# FE_LED.net
KiCad netlist of a schematic drawn in EAGLE
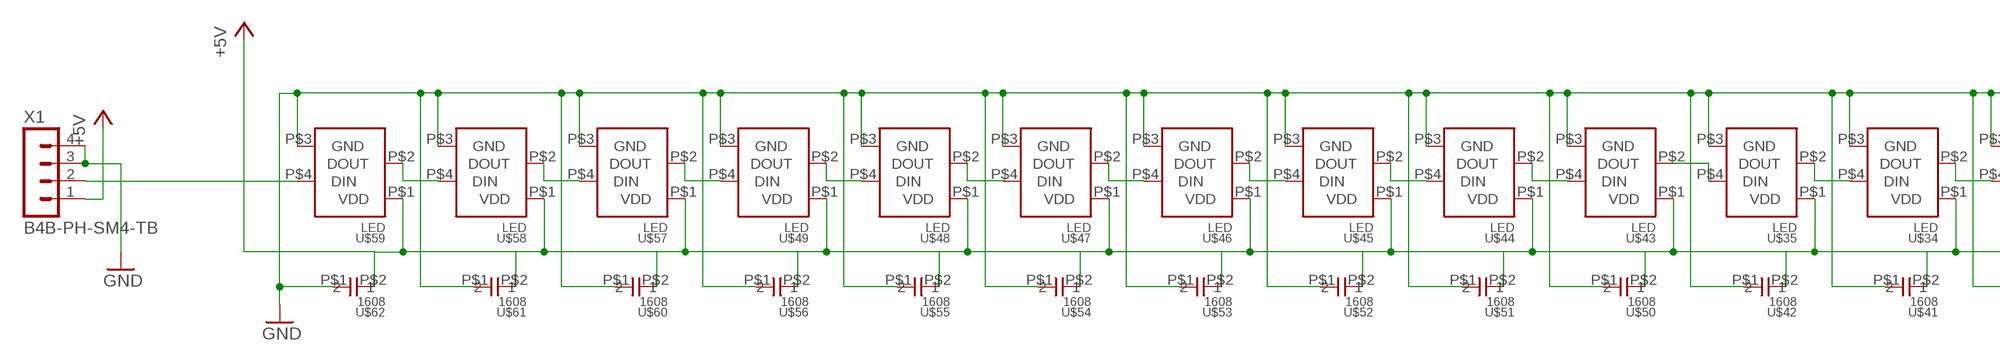
[diagram p0: schematic, sheet 1, part 1 of 2]
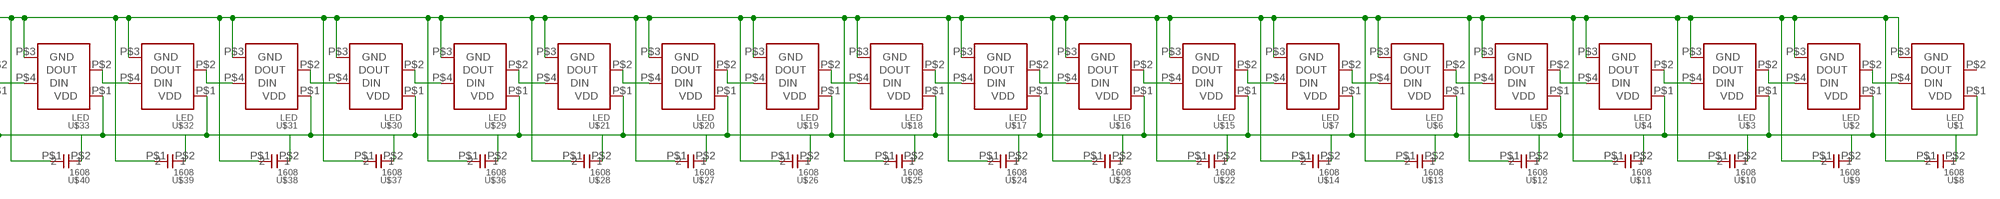
[diagram p1: schematic, sheet 1, part 2 of 2]

(export (version "E")
  (design (tool "Eeschema 10.0.6"))
  (components
    (comp (ref "U$1")
      (value "LED")
      (footprint "eagle-import:LED")
      (libsource (lib "eagle-import") (part "LED"))
    )
    (comp (ref "U$2")
      (value "LED")
      (footprint "eagle-import:LED")
      (libsource (lib "eagle-import") (part "LED"))
    )
    (comp (ref "U$3")
      (value "LED")
      (footprint "eagle-import:LED")
      (libsource (lib "eagle-import") (part "LED"))
    )
    (comp (ref "U$4")
      (value "LED")
      (footprint "eagle-import:LED")
      (libsource (lib "eagle-import") (part "LED"))
    )
    (comp (ref "U$5")
      (value "LED")
      (footprint "eagle-import:LED")
      (libsource (lib "eagle-import") (part "LED"))
    )
    (comp (ref "U$6")
      (value "LED")
      (footprint "eagle-import:LED")
      (libsource (lib "eagle-import") (part "LED"))
    )
    (comp (ref "U$7")
      (value "LED")
      (footprint "eagle-import:LED")
      (libsource (lib "eagle-import") (part "LED"))
    )
    (comp (ref "U$8")
      (value "1608")
      (footprint "eagle-import:CON")
      (libsource (lib "eagle-import") (part "1608"))
    )
    (comp (ref "U$9")
      (value "1608")
      (footprint "eagle-import:CON")
      (libsource (lib "eagle-import") (part "1608"))
    )
    (comp (ref "U$10")
      (value "1608")
      (footprint "eagle-import:CON")
      (libsource (lib "eagle-import") (part "1608"))
    )
    (comp (ref "U$11")
      (value "1608")
      (footprint "eagle-import:CON")
      (libsource (lib "eagle-import") (part "1608"))
    )
    (comp (ref "U$12")
      (value "1608")
      (footprint "eagle-import:CON")
      (libsource (lib "eagle-import") (part "1608"))
    )
    (comp (ref "U$13")
      (value "1608")
      (footprint "eagle-import:CON")
      (libsource (lib "eagle-import") (part "1608"))
    )
    (comp (ref "U$14")
      (value "1608")
      (footprint "eagle-import:CON")
      (libsource (lib "eagle-import") (part "1608"))
    )
    (comp (ref "U$15")
      (value "LED")
      (footprint "eagle-import:LED")
      (libsource (lib "eagle-import") (part "LED"))
    )
    (comp (ref "U$16")
      (value "LED")
      (footprint "eagle-import:LED")
      (libsource (lib "eagle-import") (part "LED"))
    )
    (comp (ref "U$17")
      (value "LED")
      (footprint "eagle-import:LED")
      (libsource (lib "eagle-import") (part "LED"))
    )
    (comp (ref "U$18")
      (value "LED")
      (footprint "eagle-import:LED")
      (libsource (lib "eagle-import") (part "LED"))
    )
    (comp (ref "U$19")
      (value "LED")
      (footprint "eagle-import:LED")
      (libsource (lib "eagle-import") (part "LED"))
    )
    (comp (ref "U$20")
      (value "LED")
      (footprint "eagle-import:LED")
      (libsource (lib "eagle-import") (part "LED"))
    )
    (comp (ref "U$21")
      (value "LED")
      (footprint "eagle-import:LED")
      (libsource (lib "eagle-import") (part "LED"))
    )
    (comp (ref "U$22")
      (value "1608")
      (footprint "eagle-import:CON")
      (libsource (lib "eagle-import") (part "1608"))
    )
    (comp (ref "U$23")
      (value "1608")
      (footprint "eagle-import:CON")
      (libsource (lib "eagle-import") (part "1608"))
    )
    (comp (ref "U$24")
      (value "1608")
      (footprint "eagle-import:CON")
      (libsource (lib "eagle-import") (part "1608"))
    )
    (comp (ref "U$25")
      (value "1608")
      (footprint "eagle-import:CON")
      (libsource (lib "eagle-import") (part "1608"))
    )
    (comp (ref "U$26")
      (value "1608")
      (footprint "eagle-import:CON")
      (libsource (lib "eagle-import") (part "1608"))
    )
    (comp (ref "U$27")
      (value "1608")
      (footprint "eagle-import:CON")
      (libsource (lib "eagle-import") (part "1608"))
    )
    (comp (ref "U$28")
      (value "1608")
      (footprint "eagle-import:CON")
      (libsource (lib "eagle-import") (part "1608"))
    )
    (comp (ref "U$29")
      (value "LED")
      (footprint "eagle-import:LED")
      (libsource (lib "eagle-import") (part "LED"))
    )
    (comp (ref "U$30")
      (value "LED")
      (footprint "eagle-import:LED")
      (libsource (lib "eagle-import") (part "LED"))
    )
    (comp (ref "U$31")
      (value "LED")
      (footprint "eagle-import:LED")
      (libsource (lib "eagle-import") (part "LED"))
    )
    (comp (ref "U$32")
      (value "LED")
      (footprint "eagle-import:LED")
      (libsource (lib "eagle-import") (part "LED"))
    )
    (comp (ref "U$33")
      (value "LED")
      (footprint "eagle-import:LED")
      (libsource (lib "eagle-import") (part "LED"))
    )
    (comp (ref "U$34")
      (value "LED")
      (footprint "eagle-import:LED")
      (libsource (lib "eagle-import") (part "LED"))
    )
    (comp (ref "U$35")
      (value "LED")
      (footprint "eagle-import:LED")
      (libsource (lib "eagle-import") (part "LED"))
    )
    (comp (ref "U$36")
      (value "1608")
      (footprint "eagle-import:CON")
      (libsource (lib "eagle-import") (part "1608"))
    )
    (comp (ref "U$37")
      (value "1608")
      (footprint "eagle-import:CON")
      (libsource (lib "eagle-import") (part "1608"))
    )
    (comp (ref "U$38")
      (value "1608")
      (footprint "eagle-import:CON")
      (libsource (lib "eagle-import") (part "1608"))
    )
    (comp (ref "U$39")
      (value "1608")
      (footprint "eagle-import:CON")
      (libsource (lib "eagle-import") (part "1608"))
    )
    (comp (ref "U$40")
      (value "1608")
      (footprint "eagle-import:CON")
      (libsource (lib "eagle-import") (part "1608"))
    )
    (comp (ref "U$41")
      (value "1608")
      (footprint "eagle-import:CON")
      (libsource (lib "eagle-import") (part "1608"))
    )
    (comp (ref "U$42")
      (value "1608")
      (footprint "eagle-import:CON")
      (libsource (lib "eagle-import") (part "1608"))
    )
    (comp (ref "U$43")
      (value "LED")
      (footprint "eagle-import:LED")
      (libsource (lib "eagle-import") (part "LED"))
    )
    (comp (ref "U$44")
      (value "LED")
      (footprint "eagle-import:LED")
      (libsource (lib "eagle-import") (part "LED"))
    )
    (comp (ref "U$45")
      (value "LED")
      (footprint "eagle-import:LED")
      (libsource (lib "eagle-import") (part "LED"))
    )
    (comp (ref "U$46")
      (value "LED")
      (footprint "eagle-import:LED")
      (libsource (lib "eagle-import") (part "LED"))
    )
    (comp (ref "U$47")
      (value "LED")
      (footprint "eagle-import:LED")
      (libsource (lib "eagle-import") (part "LED"))
    )
    (comp (ref "U$48")
      (value "LED")
      (footprint "eagle-import:LED")
      (libsource (lib "eagle-import") (part "LED"))
    )
    (comp (ref "U$49")
      (value "LED")
      (footprint "eagle-import:LED")
      (libsource (lib "eagle-import") (part "LED"))
    )
    (comp (ref "U$50")
      (value "1608")
      (footprint "eagle-import:CON")
      (libsource (lib "eagle-import") (part "1608"))
    )
    (comp (ref "U$51")
      (value "1608")
      (footprint "eagle-import:CON")
      (libsource (lib "eagle-import") (part "1608"))
    )
    (comp (ref "U$52")
      (value "1608")
      (footprint "eagle-import:CON")
      (libsource (lib "eagle-import") (part "1608"))
    )
    (comp (ref "U$53")
      (value "1608")
      (footprint "eagle-import:CON")
      (libsource (lib "eagle-import") (part "1608"))
    )
    (comp (ref "U$54")
      (value "1608")
      (footprint "eagle-import:CON")
      (libsource (lib "eagle-import") (part "1608"))
    )
    (comp (ref "U$55")
      (value "1608")
      (footprint "eagle-import:CON")
      (libsource (lib "eagle-import") (part "1608"))
    )
    (comp (ref "U$56")
      (value "1608")
      (footprint "eagle-import:CON")
      (libsource (lib "eagle-import") (part "1608"))
    )
    (comp (ref "U$57")
      (value "LED")
      (footprint "eagle-import:LED")
      (libsource (lib "eagle-import") (part "LED"))
    )
    (comp (ref "U$58")
      (value "LED")
      (footprint "eagle-import:LED")
      (libsource (lib "eagle-import") (part "LED"))
    )
    (comp (ref "U$59")
      (value "LED")
      (footprint "eagle-import:LED")
      (libsource (lib "eagle-import") (part "LED"))
    )
    (comp (ref "U$60")
      (value "1608")
      (footprint "eagle-import:CON")
      (libsource (lib "eagle-import") (part "1608"))
    )
    (comp (ref "U$61")
      (value "1608")
      (footprint "eagle-import:CON")
      (libsource (lib "eagle-import") (part "1608"))
    )
    (comp (ref "U$62")
      (value "1608")
      (footprint "eagle-import:CON")
      (libsource (lib "eagle-import") (part "1608"))
    )
    (comp (ref "X1")
      (value "B4B-PH-SM4-TB")
      (footprint "eagle-import:B4B-PH-SM4-TB")
      (libsource (lib "eagle-import") (part "B4B-PH-SM4-TB"))
    )
  )
  (nets
    (net (code "1") (name "+5V") (class "Default")
      (node (ref "U$1") (pin "P$1") (pinfunction "VDD_P$1") (pintype "bidirectional"))
      (node (ref "U$10") (pin "P$2") (pinfunction "2_P$2") (pintype "bidirectional"))
      (node (ref "U$11") (pin "P$2") (pinfunction "2_P$2") (pintype "bidirectional"))
      (node (ref "U$12") (pin "P$2") (pinfunction "2_P$2") (pintype "bidirectional"))
      (node (ref "U$13") (pin "P$2") (pinfunction "2_P$2") (pintype "bidirectional"))
      (node (ref "U$14") (pin "P$2") (pinfunction "2_P$2") (pintype "bidirectional"))
      (node (ref "U$15") (pin "P$1") (pinfunction "VDD_P$1") (pintype "bidirectional"))
      (node (ref "U$16") (pin "P$1") (pinfunction "VDD_P$1") (pintype "bidirectional"))
      (node (ref "U$17") (pin "P$1") (pinfunction "VDD_P$1") (pintype "bidirectional"))
      (node (ref "U$18") (pin "P$1") (pinfunction "VDD_P$1") (pintype "bidirectional"))
      (node (ref "U$19") (pin "P$1") (pinfunction "VDD_P$1") (pintype "bidirectional"))
      (node (ref "U$2") (pin "P$1") (pinfunction "VDD_P$1") (pintype "bidirectional"))
      (node (ref "U$20") (pin "P$1") (pinfunction "VDD_P$1") (pintype "bidirectional"))
      (node (ref "U$21") (pin "P$1") (pinfunction "VDD_P$1") (pintype "bidirectional"))
      (node (ref "U$22") (pin "P$2") (pinfunction "2_P$2") (pintype "bidirectional"))
      (node (ref "U$23") (pin "P$2") (pinfunction "2_P$2") (pintype "bidirectional"))
      (node (ref "U$24") (pin "P$2") (pinfunction "2_P$2") (pintype "bidirectional"))
      (node (ref "U$25") (pin "P$2") (pinfunction "2_P$2") (pintype "bidirectional"))
      (node (ref "U$26") (pin "P$2") (pinfunction "2_P$2") (pintype "bidirectional"))
      (node (ref "U$27") (pin "P$2") (pinfunction "2_P$2") (pintype "bidirectional"))
      (node (ref "U$28") (pin "P$2") (pinfunction "2_P$2") (pintype "bidirectional"))
      (node (ref "U$29") (pin "P$1") (pinfunction "VDD_P$1") (pintype "bidirectional"))
      (node (ref "U$3") (pin "P$1") (pinfunction "VDD_P$1") (pintype "bidirectional"))
      (node (ref "U$30") (pin "P$1") (pinfunction "VDD_P$1") (pintype "bidirectional"))
      (node (ref "U$31") (pin "P$1") (pinfunction "VDD_P$1") (pintype "bidirectional"))
      (node (ref "U$32") (pin "P$1") (pinfunction "VDD_P$1") (pintype "bidirectional"))
      (node (ref "U$33") (pin "P$1") (pinfunction "VDD_P$1") (pintype "bidirectional"))
      (node (ref "U$34") (pin "P$1") (pinfunction "VDD_P$1") (pintype "bidirectional"))
      (node (ref "U$35") (pin "P$1") (pinfunction "VDD_P$1") (pintype "bidirectional"))
      (node (ref "U$36") (pin "P$2") (pinfunction "2_P$2") (pintype "bidirectional"))
      (node (ref "U$37") (pin "P$2") (pinfunction "2_P$2") (pintype "bidirectional"))
      (node (ref "U$38") (pin "P$2") (pinfunction "2_P$2") (pintype "bidirectional"))
      (node (ref "U$39") (pin "P$2") (pinfunction "2_P$2") (pintype "bidirectional"))
      (node (ref "U$4") (pin "P$1") (pinfunction "VDD_P$1") (pintype "bidirectional"))
      (node (ref "U$40") (pin "P$2") (pinfunction "2_P$2") (pintype "bidirectional"))
      (node (ref "U$41") (pin "P$2") (pinfunction "2_P$2") (pintype "bidirectional"))
      (node (ref "U$42") (pin "P$2") (pinfunction "2_P$2") (pintype "bidirectional"))
      (node (ref "U$43") (pin "P$1") (pinfunction "VDD_P$1") (pintype "bidirectional"))
      (node (ref "U$44") (pin "P$1") (pinfunction "VDD_P$1") (pintype "bidirectional"))
      (node (ref "U$45") (pin "P$1") (pinfunction "VDD_P$1") (pintype "bidirectional"))
      (node (ref "U$46") (pin "P$1") (pinfunction "VDD_P$1") (pintype "bidirectional"))
      (node (ref "U$47") (pin "P$1") (pinfunction "VDD_P$1") (pintype "bidirectional"))
      (node (ref "U$48") (pin "P$1") (pinfunction "VDD_P$1") (pintype "bidirectional"))
      (node (ref "U$49") (pin "P$1") (pinfunction "VDD_P$1") (pintype "bidirectional"))
      (node (ref "U$5") (pin "P$1") (pinfunction "VDD_P$1") (pintype "bidirectional"))
      (node (ref "U$50") (pin "P$2") (pinfunction "2_P$2") (pintype "bidirectional"))
      (node (ref "U$51") (pin "P$2") (pinfunction "2_P$2") (pintype "bidirectional"))
      (node (ref "U$52") (pin "P$2") (pinfunction "2_P$2") (pintype "bidirectional"))
      (node (ref "U$53") (pin "P$2") (pinfunction "2_P$2") (pintype "bidirectional"))
      (node (ref "U$54") (pin "P$2") (pinfunction "2_P$2") (pintype "bidirectional"))
      (node (ref "U$55") (pin "P$2") (pinfunction "2_P$2") (pintype "bidirectional"))
      (node (ref "U$56") (pin "P$2") (pinfunction "2_P$2") (pintype "bidirectional"))
      (node (ref "U$57") (pin "P$1") (pinfunction "VDD_P$1") (pintype "bidirectional"))
      (node (ref "U$58") (pin "P$1") (pinfunction "VDD_P$1") (pintype "bidirectional"))
      (node (ref "U$59") (pin "P$1") (pinfunction "VDD_P$1") (pintype "bidirectional"))
      (node (ref "U$6") (pin "P$1") (pinfunction "VDD_P$1") (pintype "bidirectional"))
      (node (ref "U$60") (pin "P$2") (pinfunction "2_P$2") (pintype "bidirectional"))
      (node (ref "U$61") (pin "P$2") (pinfunction "2_P$2") (pintype "bidirectional"))
      (node (ref "U$62") (pin "P$2") (pinfunction "2_P$2") (pintype "bidirectional"))
      (node (ref "U$7") (pin "P$1") (pinfunction "VDD_P$1") (pintype "bidirectional"))
      (node (ref "U$8") (pin "P$2") (pinfunction "2_P$2") (pintype "bidirectional"))
      (node (ref "U$9") (pin "P$2") (pinfunction "2_P$2") (pintype "bidirectional"))
      (node (ref "X1") (pin "1") (pinfunction "1_1") (pintype "passive"))
    )
    (net (code "2") (name "GND") (class "Default")
      (node (ref "U$1") (pin "P$3") (pinfunction "GND_P$3") (pintype "bidirectional"))
      (node (ref "U$10") (pin "P$1") (pinfunction "1_P$1") (pintype "bidirectional"))
      (node (ref "U$11") (pin "P$1") (pinfunction "1_P$1") (pintype "bidirectional"))
      (node (ref "U$12") (pin "P$1") (pinfunction "1_P$1") (pintype "bidirectional"))
      (node (ref "U$13") (pin "P$1") (pinfunction "1_P$1") (pintype "bidirectional"))
      (node (ref "U$14") (pin "P$1") (pinfunction "1_P$1") (pintype "bidirectional"))
      (node (ref "U$15") (pin "P$3") (pinfunction "GND_P$3") (pintype "bidirectional"))
      (node (ref "U$16") (pin "P$3") (pinfunction "GND_P$3") (pintype "bidirectional"))
      (node (ref "U$17") (pin "P$3") (pinfunction "GND_P$3") (pintype "bidirectional"))
      (node (ref "U$18") (pin "P$3") (pinfunction "GND_P$3") (pintype "bidirectional"))
      (node (ref "U$19") (pin "P$3") (pinfunction "GND_P$3") (pintype "bidirectional"))
      (node (ref "U$2") (pin "P$3") (pinfunction "GND_P$3") (pintype "bidirectional"))
      (node (ref "U$20") (pin "P$3") (pinfunction "GND_P$3") (pintype "bidirectional"))
      (node (ref "U$21") (pin "P$3") (pinfunction "GND_P$3") (pintype "bidirectional"))
      (node (ref "U$22") (pin "P$1") (pinfunction "1_P$1") (pintype "bidirectional"))
      (node (ref "U$23") (pin "P$1") (pinfunction "1_P$1") (pintype "bidirectional"))
      (node (ref "U$24") (pin "P$1") (pinfunction "1_P$1") (pintype "bidirectional"))
      (node (ref "U$25") (pin "P$1") (pinfunction "1_P$1") (pintype "bidirectional"))
      (node (ref "U$26") (pin "P$1") (pinfunction "1_P$1") (pintype "bidirectional"))
      (node (ref "U$27") (pin "P$1") (pinfunction "1_P$1") (pintype "bidirectional"))
      (node (ref "U$28") (pin "P$1") (pinfunction "1_P$1") (pintype "bidirectional"))
      (node (ref "U$29") (pin "P$3") (pinfunction "GND_P$3") (pintype "bidirectional"))
      (node (ref "U$3") (pin "P$3") (pinfunction "GND_P$3") (pintype "bidirectional"))
      (node (ref "U$30") (pin "P$3") (pinfunction "GND_P$3") (pintype "bidirectional"))
      (node (ref "U$31") (pin "P$3") (pinfunction "GND_P$3") (pintype "bidirectional"))
      (node (ref "U$32") (pin "P$3") (pinfunction "GND_P$3") (pintype "bidirectional"))
      (node (ref "U$33") (pin "P$3") (pinfunction "GND_P$3") (pintype "bidirectional"))
      (node (ref "U$34") (pin "P$3") (pinfunction "GND_P$3") (pintype "bidirectional"))
      (node (ref "U$35") (pin "P$3") (pinfunction "GND_P$3") (pintype "bidirectional"))
      (node (ref "U$36") (pin "P$1") (pinfunction "1_P$1") (pintype "bidirectional"))
      (node (ref "U$37") (pin "P$1") (pinfunction "1_P$1") (pintype "bidirectional"))
      (node (ref "U$38") (pin "P$1") (pinfunction "1_P$1") (pintype "bidirectional"))
      (node (ref "U$39") (pin "P$1") (pinfunction "1_P$1") (pintype "bidirectional"))
      (node (ref "U$4") (pin "P$3") (pinfunction "GND_P$3") (pintype "bidirectional"))
      (node (ref "U$40") (pin "P$1") (pinfunction "1_P$1") (pintype "bidirectional"))
      (node (ref "U$41") (pin "P$1") (pinfunction "1_P$1") (pintype "bidirectional"))
      (node (ref "U$42") (pin "P$1") (pinfunction "1_P$1") (pintype "bidirectional"))
      (node (ref "U$43") (pin "P$3") (pinfunction "GND_P$3") (pintype "bidirectional"))
      (node (ref "U$44") (pin "P$3") (pinfunction "GND_P$3") (pintype "bidirectional"))
      (node (ref "U$45") (pin "P$3") (pinfunction "GND_P$3") (pintype "bidirectional"))
      (node (ref "U$46") (pin "P$3") (pinfunction "GND_P$3") (pintype "bidirectional"))
      (node (ref "U$47") (pin "P$3") (pinfunction "GND_P$3") (pintype "bidirectional"))
      (node (ref "U$48") (pin "P$3") (pinfunction "GND_P$3") (pintype "bidirectional"))
      (node (ref "U$49") (pin "P$3") (pinfunction "GND_P$3") (pintype "bidirectional"))
      (node (ref "U$5") (pin "P$3") (pinfunction "GND_P$3") (pintype "bidirectional"))
      (node (ref "U$50") (pin "P$1") (pinfunction "1_P$1") (pintype "bidirectional"))
      (node (ref "U$51") (pin "P$1") (pinfunction "1_P$1") (pintype "bidirectional"))
      (node (ref "U$52") (pin "P$1") (pinfunction "1_P$1") (pintype "bidirectional"))
      (node (ref "U$53") (pin "P$1") (pinfunction "1_P$1") (pintype "bidirectional"))
      (node (ref "U$54") (pin "P$1") (pinfunction "1_P$1") (pintype "bidirectional"))
      (node (ref "U$55") (pin "P$1") (pinfunction "1_P$1") (pintype "bidirectional"))
      (node (ref "U$56") (pin "P$1") (pinfunction "1_P$1") (pintype "bidirectional"))
      (node (ref "U$57") (pin "P$3") (pinfunction "GND_P$3") (pintype "bidirectional"))
      (node (ref "U$58") (pin "P$3") (pinfunction "GND_P$3") (pintype "bidirectional"))
      (node (ref "U$59") (pin "P$3") (pinfunction "GND_P$3") (pintype "bidirectional"))
      (node (ref "U$6") (pin "P$3") (pinfunction "GND_P$3") (pintype "bidirectional"))
      (node (ref "U$60") (pin "P$1") (pinfunction "1_P$1") (pintype "bidirectional"))
      (node (ref "U$61") (pin "P$1") (pinfunction "1_P$1") (pintype "bidirectional"))
      (node (ref "U$62") (pin "P$1") (pinfunction "1_P$1") (pintype "bidirectional"))
      (node (ref "U$7") (pin "P$3") (pinfunction "GND_P$3") (pintype "bidirectional"))
      (node (ref "U$8") (pin "P$1") (pinfunction "1_P$1") (pintype "bidirectional"))
      (node (ref "U$9") (pin "P$1") (pinfunction "1_P$1") (pintype "bidirectional"))
      (node (ref "X1") (pin "3") (pinfunction "3_3") (pintype "passive"))
      (node (ref "X1") (pin "4") (pinfunction "4_4") (pintype "passive"))
    )
    (net (code "3") (name "Net-(U$1-DIN)") (class "Default")
      (node (ref "U$1") (pin "P$4") (pinfunction "DIN_P$4") (pintype "bidirectional"))
      (node (ref "U$2") (pin "P$2") (pinfunction "DOUT_P$2") (pintype "bidirectional"))
    )
    (net (code "4") (name "Net-(U$2-DIN)") (class "Default")
      (node (ref "U$2") (pin "P$4") (pinfunction "DIN_P$4") (pintype "bidirectional"))
      (node (ref "U$3") (pin "P$2") (pinfunction "DOUT_P$2") (pintype "bidirectional"))
    )
    (net (code "5") (name "Net-(U$3-DIN)") (class "Default")
      (node (ref "U$3") (pin "P$4") (pinfunction "DIN_P$4") (pintype "bidirectional"))
      (node (ref "U$4") (pin "P$2") (pinfunction "DOUT_P$2") (pintype "bidirectional"))
    )
    (net (code "6") (name "Net-(U$4-DIN)") (class "Default")
      (node (ref "U$4") (pin "P$4") (pinfunction "DIN_P$4") (pintype "bidirectional"))
      (node (ref "U$5") (pin "P$2") (pinfunction "DOUT_P$2") (pintype "bidirectional"))
    )
    (net (code "7") (name "Net-(U$5-DIN)") (class "Default")
      (node (ref "U$5") (pin "P$4") (pinfunction "DIN_P$4") (pintype "bidirectional"))
      (node (ref "U$6") (pin "P$2") (pinfunction "DOUT_P$2") (pintype "bidirectional"))
    )
    (net (code "8") (name "Net-(U$6-DIN)") (class "Default")
      (node (ref "U$6") (pin "P$4") (pinfunction "DIN_P$4") (pintype "bidirectional"))
      (node (ref "U$7") (pin "P$2") (pinfunction "DOUT_P$2") (pintype "bidirectional"))
    )
    (net (code "9") (name "Net-(U$15-DIN)") (class "Default")
      (node (ref "U$15") (pin "P$4") (pinfunction "DIN_P$4") (pintype "bidirectional"))
      (node (ref "U$16") (pin "P$2") (pinfunction "DOUT_P$2") (pintype "bidirectional"))
    )
    (net (code "10") (name "Net-(U$15-DOUT)") (class "Default")
      (node (ref "U$15") (pin "P$2") (pinfunction "DOUT_P$2") (pintype "bidirectional"))
      (node (ref "U$7") (pin "P$4") (pinfunction "DIN_P$4") (pintype "bidirectional"))
    )
    (net (code "11") (name "Net-(U$16-DIN)") (class "Default")
      (node (ref "U$16") (pin "P$4") (pinfunction "DIN_P$4") (pintype "bidirectional"))
      (node (ref "U$17") (pin "P$2") (pinfunction "DOUT_P$2") (pintype "bidirectional"))
    )
    (net (code "12") (name "Net-(U$17-DIN)") (class "Default")
      (node (ref "U$17") (pin "P$4") (pinfunction "DIN_P$4") (pintype "bidirectional"))
      (node (ref "U$18") (pin "P$2") (pinfunction "DOUT_P$2") (pintype "bidirectional"))
    )
    (net (code "13") (name "Net-(U$18-DIN)") (class "Default")
      (node (ref "U$18") (pin "P$4") (pinfunction "DIN_P$4") (pintype "bidirectional"))
      (node (ref "U$19") (pin "P$2") (pinfunction "DOUT_P$2") (pintype "bidirectional"))
    )
    (net (code "14") (name "Net-(U$19-DIN)") (class "Default")
      (node (ref "U$19") (pin "P$4") (pinfunction "DIN_P$4") (pintype "bidirectional"))
      (node (ref "U$20") (pin "P$2") (pinfunction "DOUT_P$2") (pintype "bidirectional"))
    )
    (net (code "15") (name "Net-(U$20-DIN)") (class "Default")
      (node (ref "U$20") (pin "P$4") (pinfunction "DIN_P$4") (pintype "bidirectional"))
      (node (ref "U$21") (pin "P$2") (pinfunction "DOUT_P$2") (pintype "bidirectional"))
    )
    (net (code "16") (name "Net-(U$21-DIN)") (class "Default")
      (node (ref "U$21") (pin "P$4") (pinfunction "DIN_P$4") (pintype "bidirectional"))
      (node (ref "U$29") (pin "P$2") (pinfunction "DOUT_P$2") (pintype "bidirectional"))
    )
    (net (code "17") (name "Net-(U$29-DIN)") (class "Default")
      (node (ref "U$29") (pin "P$4") (pinfunction "DIN_P$4") (pintype "bidirectional"))
      (node (ref "U$30") (pin "P$2") (pinfunction "DOUT_P$2") (pintype "bidirectional"))
    )
    (net (code "18") (name "Net-(U$30-DIN)") (class "Default")
      (node (ref "U$30") (pin "P$4") (pinfunction "DIN_P$4") (pintype "bidirectional"))
      (node (ref "U$31") (pin "P$2") (pinfunction "DOUT_P$2") (pintype "bidirectional"))
    )
    (net (code "19") (name "Net-(U$31-DIN)") (class "Default")
      (node (ref "U$31") (pin "P$4") (pinfunction "DIN_P$4") (pintype "bidirectional"))
      (node (ref "U$32") (pin "P$2") (pinfunction "DOUT_P$2") (pintype "bidirectional"))
    )
    (net (code "20") (name "Net-(U$32-DIN)") (class "Default")
      (node (ref "U$32") (pin "P$4") (pinfunction "DIN_P$4") (pintype "bidirectional"))
      (node (ref "U$33") (pin "P$2") (pinfunction "DOUT_P$2") (pintype "bidirectional"))
    )
    (net (code "21") (name "Net-(U$33-DIN)") (class "Default")
      (node (ref "U$33") (pin "P$4") (pinfunction "DIN_P$4") (pintype "bidirectional"))
      (node (ref "U$34") (pin "P$2") (pinfunction "DOUT_P$2") (pintype "bidirectional"))
    )
    (net (code "22") (name "Net-(U$34-DIN)") (class "Default")
      (node (ref "U$34") (pin "P$4") (pinfunction "DIN_P$4") (pintype "bidirectional"))
      (node (ref "U$35") (pin "P$2") (pinfunction "DOUT_P$2") (pintype "bidirectional"))
    )
    (net (code "23") (name "Net-(U$35-DIN)") (class "Default")
      (node (ref "U$35") (pin "P$4") (pinfunction "DIN_P$4") (pintype "bidirectional"))
      (node (ref "U$43") (pin "P$2") (pinfunction "DOUT_P$2") (pintype "bidirectional"))
    )
    (net (code "24") (name "Net-(U$43-DIN)") (class "Default")
      (node (ref "U$43") (pin "P$4") (pinfunction "DIN_P$4") (pintype "bidirectional"))
      (node (ref "U$44") (pin "P$2") (pinfunction "DOUT_P$2") (pintype "bidirectional"))
    )
    (net (code "25") (name "Net-(U$44-DIN)") (class "Default")
      (node (ref "U$44") (pin "P$4") (pinfunction "DIN_P$4") (pintype "bidirectional"))
      (node (ref "U$45") (pin "P$2") (pinfunction "DOUT_P$2") (pintype "bidirectional"))
    )
    (net (code "26") (name "Net-(U$45-DIN)") (class "Default")
      (node (ref "U$45") (pin "P$4") (pinfunction "DIN_P$4") (pintype "bidirectional"))
      (node (ref "U$46") (pin "P$2") (pinfunction "DOUT_P$2") (pintype "bidirectional"))
    )
    (net (code "27") (name "Net-(U$46-DIN)") (class "Default")
      (node (ref "U$46") (pin "P$4") (pinfunction "DIN_P$4") (pintype "bidirectional"))
      (node (ref "U$47") (pin "P$2") (pinfunction "DOUT_P$2") (pintype "bidirectional"))
    )
    (net (code "28") (name "Net-(U$47-DIN)") (class "Default")
      (node (ref "U$47") (pin "P$4") (pinfunction "DIN_P$4") (pintype "bidirectional"))
      (node (ref "U$48") (pin "P$2") (pinfunction "DOUT_P$2") (pintype "bidirectional"))
    )
    (net (code "29") (name "Net-(U$48-DIN)") (class "Default")
      (node (ref "U$48") (pin "P$4") (pinfunction "DIN_P$4") (pintype "bidirectional"))
      (node (ref "U$49") (pin "P$2") (pinfunction "DOUT_P$2") (pintype "bidirectional"))
    )
    (net (code "30") (name "Net-(U$49-DIN)") (class "Default")
      (node (ref "U$49") (pin "P$4") (pinfunction "DIN_P$4") (pintype "bidirectional"))
      (node (ref "U$57") (pin "P$2") (pinfunction "DOUT_P$2") (pintype "bidirectional"))
    )
    (net (code "31") (name "Net-(U$57-DIN)") (class "Default")
      (node (ref "U$57") (pin "P$4") (pinfunction "DIN_P$4") (pintype "bidirectional"))
      (node (ref "U$58") (pin "P$2") (pinfunction "DOUT_P$2") (pintype "bidirectional"))
    )
    (net (code "32") (name "Net-(U$58-DIN)") (class "Default")
      (node (ref "U$58") (pin "P$4") (pinfunction "DIN_P$4") (pintype "bidirectional"))
      (node (ref "U$59") (pin "P$2") (pinfunction "DOUT_P$2") (pintype "bidirectional"))
    )
    (net (code "33") (name "Net-(U$59-DIN)") (class "Default")
      (node (ref "U$59") (pin "P$4") (pinfunction "DIN_P$4") (pintype "bidirectional"))
      (node (ref "X1") (pin "2") (pinfunction "2_2") (pintype "passive"))
    )
    (net (code "34") (name "unconnected-(U$1-DOUT-PadP$2)") (class "Default")
      (node (ref "U$1") (pin "P$2") (pinfunction "DOUT_P$2") (pintype "bidirectional"))
    )
  )
)
